# CH32V303VCT6-R1.net
KiCad netlist of a schematic drawn in Altium Designer
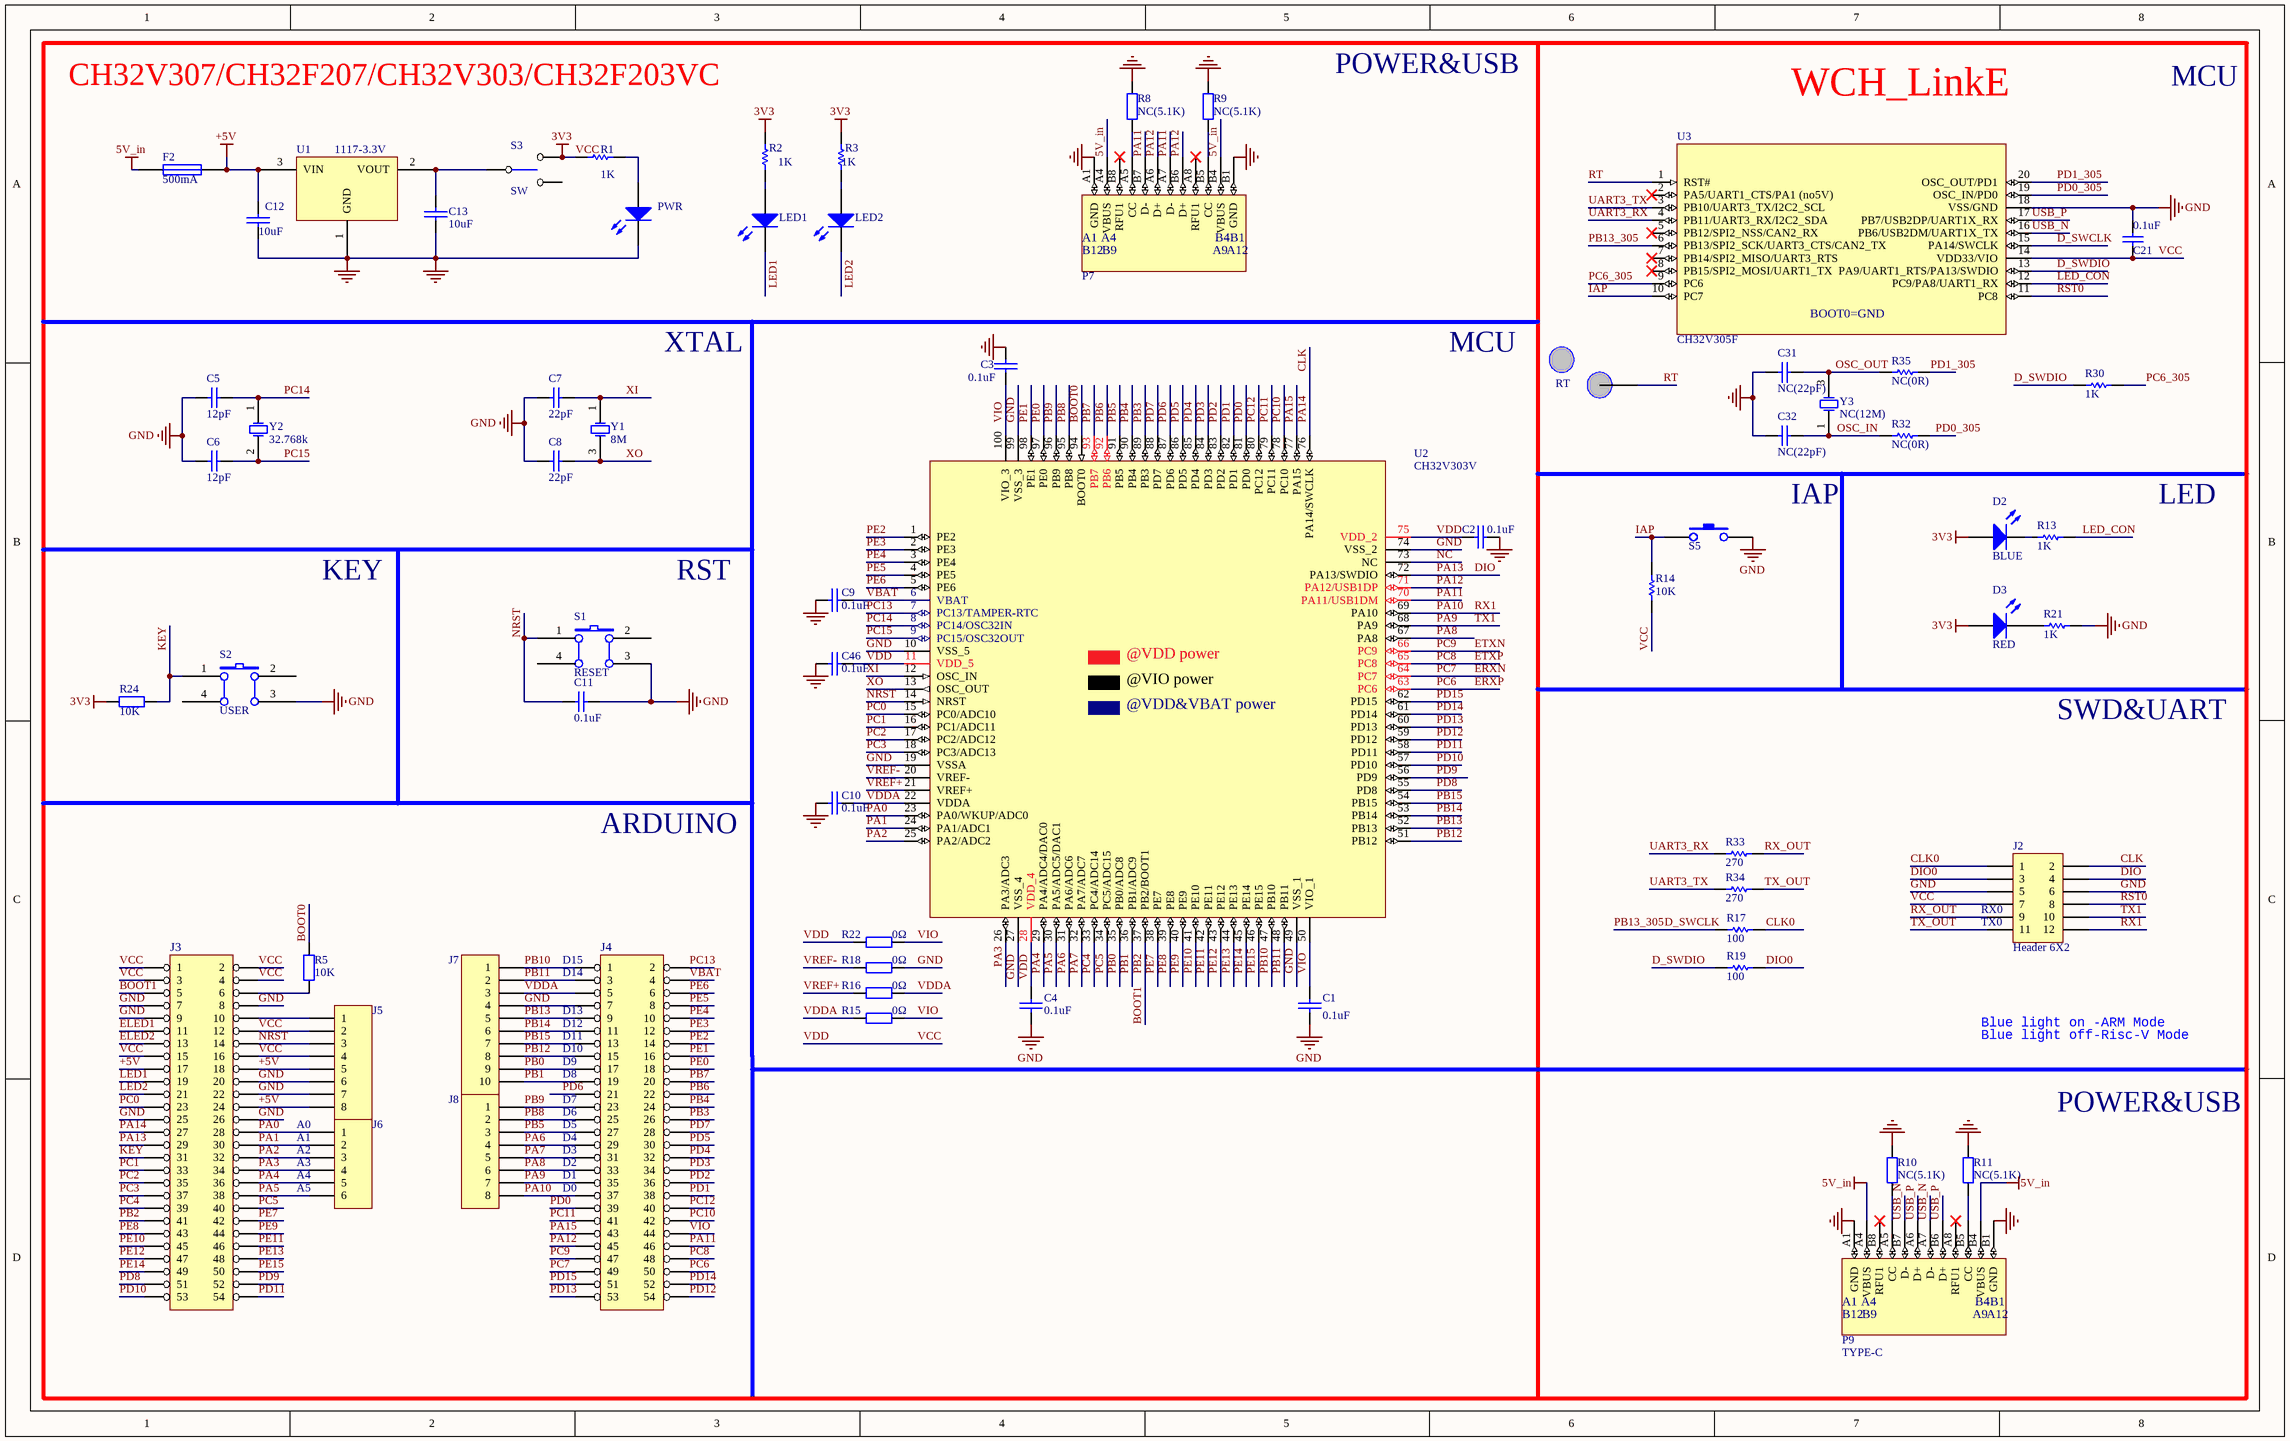
[diagram p0: CH32V303VCT6-R1.SchDoc]

(export (version "E")
  (design (tool "Eeschema 10.0.6"))
  (components
    (comp (ref "C1")
      (value "0.1uF")
      (footprint "0603_C")
      (description "Capacitor")
      (libsource (lib "*") (part "CAP"))
    )
    (comp (ref "C2")
      (value "0.1uF")
      (footprint "0603_C")
      (description "Capacitor")
      (libsource (lib "*") (part "CAP"))
    )
    (comp (ref "C3")
      (value "0.1uF")
      (footprint "0603_C")
      (description "Capacitor")
      (libsource (lib "*") (part "CAP"))
    )
    (comp (ref "C4")
      (value "0.1uF")
      (footprint "0603_C")
      (description "Capacitor")
      (libsource (lib "*") (part "CAP"))
    )
    (comp (ref "C5")
      (value "12pF")
      (footprint "0603_C")
      (description "Capacitor")
      (libsource (lib "Miscellaneous Devices") (part "Cap"))
    )
    (comp (ref "C6")
      (value "12pF")
      (footprint "0603_C")
      (description "Capacitor")
      (libsource (lib "Miscellaneous Devices") (part "Cap"))
    )
    (comp (ref "C7")
      (value "22pF")
      (footprint "0603_C")
      (description "Capacitor")
      (libsource (lib "Miscellaneous Devices") (part "Cap"))
    )
    (comp (ref "C8")
      (value "22pF")
      (footprint "0603_C")
      (description "Capacitor")
      (libsource (lib "Miscellaneous Devices") (part "Cap"))
    )
    (comp (ref "C9")
      (value "0.1uF")
      (footprint "0603_C")
      (description "Capacitor")
      (libsource (lib "*") (part "CAP"))
    )
    (comp (ref "C10")
      (value "0.1uF")
      (footprint "0603_C")
      (description "Capacitor")
      (libsource (lib "*") (part "CAP"))
    )
    (comp (ref "C11")
      (value "0.1uF")
      (footprint "0603_C")
      (description "Capacitor")
      (libsource (lib "Miscellaneous Devices") (part "Cap"))
    )
    (comp (ref "C12")
      (value "10uF")
      (footprint "3216_C")
      (description "Capacitor")
      (libsource (lib "*") (part "CAP"))
    )
    (comp (ref "C13")
      (value "10uF")
      (footprint "3216_C")
      (description "Capacitor")
      (libsource (lib "*") (part "CAP"))
    )
    (comp (ref "C21")
      (value "0.1uF")
      (footprint "0603_C")
      (description "Capacitor")
      (libsource (lib "Miscellaneous Devices") (part "Cap"))
    )
    (comp (ref "C31")
      (value "NC(22pF)")
      (footprint "0603_C")
      (description "Capacitor")
      (fields (field (name "PUBLISHER") "Altium Limited"))
      (libsource (lib "*") (part "Cap"))
    )
    (comp (ref "C32")
      (value "NC(22pF)")
      (footprint "0603_C")
      (description "Capacitor")
      (fields (field (name "PUBLISHER") "Altium Limited"))
      (libsource (lib "*") (part "Cap"))
    )
    (comp (ref "C46")
      (value "0.1uF")
      (footprint "0603_C")
      (description "Capacitor")
      (libsource (lib "*") (part "CAP"))
    )
    (comp (ref "D2")
      (value "BLUE")
      (footprint "0603+")
      (description "Typical RED, GREEN, YELLOW, AMBER GaAs LED")
      (fields (field (name "PUBLISHER") "Altium Limited"))
      (libsource (lib "MYLIB") (part "D0603"))
    )
    (comp (ref "D3")
      (value "RED")
      (footprint "0603+")
      (description "Typical RED, GREEN, YELLOW, AMBER GaAs LED")
      (fields (field (name "PUBLISHER") "Altium Limited"))
      (libsource (lib "MYLIB") (part "D0603"))
    )
    (comp (ref "F2")
      (value "500mA")
      (footprint "0805")
      (description "Fuse")
      (libsource (lib "*") (part "FUSE1"))
    )
    (comp (ref "J2")
      (value "Header 6X2")
      (footprint "IDC12-2.54mm")
      (description "Header, 6-Pin, Dual row")
      (fields (field (name "PUBLISHER") "Altium Limited"))
      (libsource (lib "Miscellaneous Connectors") (part "Header 6X2"))
    )
    (comp (ref "J3")
      (value "HEADER 27x2")
      (footprint "MYPCB:IDC54-2.54MM")
      (description "Header, 27-Pin, Dual row")
      (libsource (lib "wch_sch_others") (part "HEADER 27x2"))
    )
    (comp (ref "J4")
      (value "HEADER 27x2")
      (footprint "MYPCB:IDC54-2.54MM")
      (description "Header, 27-Pin, Dual row")
      (libsource (lib "wch_sch_others") (part "HEADER 27x2"))
    )
    (comp (ref "J5")
      (value "Header 8")
      (footprint "SIP8-2.54mm")
      (description "Header, 8-Pin")
      (fields (field (name "PUBLISHER") "Altium Limited"))
      (libsource (lib "Miscellaneous Connectors") (part "Header 8"))
    )
    (comp (ref "J6")
      (value "Header 6")
      (footprint "SIP6-2.54MM")
      (description "Header, 6-Pin")
      (fields (field (name "PUBLISHER") "Altium Limited"))
      (libsource (lib "Miscellaneous Connectors") (part "Header 6"))
    )
    (comp (ref "J7")
      (value "Header 10")
      (footprint "SIP10-2.54mm")
      (description "Header, 10-Pin")
      (fields (field (name "PUBLISHER") "Altium Limited"))
      (libsource (lib "Miscellaneous Connectors") (part "Header 10"))
    )
    (comp (ref "J8")
      (value "Header 8")
      (footprint "SIP8-2.54mm")
      (description "Header, 8-Pin")
      (fields (field (name "PUBLISHER") "Altium Limited"))
      (libsource (lib "") (part "Header 8_1"))
    )
    (comp (ref "LED1")
      (value "LED1   blue")
      (footprint "0603+")
      (description "Typical INFRARED GaAs LED")
      (fields (field (name "PUBLISHER") "Altium Limited"))
      (libsource (lib "Miscellaneous Devices") (part "LED0"))
    )
    (comp (ref "LED2")
      (value "LED2  blue")
      (footprint "0603+")
      (description "Typical INFRARED GaAs LED")
      (fields (field (name "PUBLISHER") "Altium Limited"))
      (libsource (lib "Miscellaneous Devices") (part "LED0"))
    )
    (comp (ref "P7")
      (value "USBFS")
      (footprint "TYPE-C-Receptacle-2.0")
      (libsource (lib "*") (part "TYPE-C1"))
    )
    (comp (ref "P9")
      (value "TYPE-C")
      (footprint "TYPE-C-Receptacle-2.0")
      (libsource (lib "*") (part "TYPE-C1"))
    )
    (comp (ref "PWR")
      (value "POWER  red")
      (footprint "0603+")
      (description "Typical INFRARED GaAs LED")
      (fields (field (name "PUBLISHER") "Altium Limited"))
      (libsource (lib "Miscellaneous Devices") (part "LED0"))
    )
    (comp (ref "R1")
      (value "1K")
      (footprint "0603")
      (description "Semiconductor Resistor")
      (libsource (lib "Miscellaneous Devices") (part "Res Semi"))
    )
    (comp (ref "R2")
      (value "1K")
      (footprint "0603")
      (description "Semiconductor Resistor")
      (libsource (lib "Miscellaneous Devices") (part "Res Semi"))
    )
    (comp (ref "R3")
      (value "1K")
      (footprint "0603")
      (description "Semiconductor Resistor")
      (libsource (lib "Miscellaneous Devices") (part "Res Semi"))
    )
    (comp (ref "R5")
      (value "10K")
      (footprint "0603")
      (description "Resistor")
      (libsource (lib "") (part "Res2_2"))
    )
    (comp (ref "R8")
      (value "NC(5.1K)")
      (footprint "0603")
      (description "Resistor")
      (libsource (lib "Miscellaneous Devices") (part "Res2"))
    )
    (comp (ref "R9")
      (value "NC(5.1K)")
      (footprint "0603")
      (description "Resistor")
      (libsource (lib "Miscellaneous Devices") (part "Res2"))
    )
    (comp (ref "R10")
      (value "NC(5.1K)")
      (footprint "0603")
      (description "Resistor")
      (libsource (lib "") (part "Res2_2"))
    )
    (comp (ref "R11")
      (value "NC(5.1K)")
      (footprint "0603")
      (description "Resistor")
      (libsource (lib "") (part "Res2_2"))
    )
    (comp (ref "R13")
      (value "1K")
      (footprint "0603")
      (description "Resistor")
      (fields (field (name "PUBLISHER") "Altium Limited"))
      (libsource (lib "MYLIB") (part "0603-1"))
    )
    (comp (ref "R14")
      (value "10K")
      (footprint "0603")
      (description "Resistor")
      (fields (field (name "PUBLISHER") "Altium Limited"))
      (libsource (lib "MYLIB") (part "0603-1"))
    )
    (comp (ref "R15")
      (value "0Ω")
      (footprint "0603")
      (description "Resistor")
      (libsource (lib "") (part "Res2_1"))
    )
    (comp (ref "R16")
      (value "0Ω")
      (footprint "0603")
      (description "Resistor")
      (libsource (lib "") (part "Res2_1"))
    )
    (comp (ref "R17")
      (value "100")
      (footprint "0603")
      (description "Resistor")
      (fields (field (name "PUBLISHER") "Altium Limited"))
      (libsource (lib "MYLIB") (part "0603-1"))
    )
    (comp (ref "R18")
      (value "0Ω")
      (footprint "0603")
      (description "Resistor")
      (libsource (lib "") (part "Res2_1"))
    )
    (comp (ref "R19")
      (value "100")
      (footprint "0603")
      (description "Resistor")
      (fields (field (name "PUBLISHER") "Altium Limited"))
      (libsource (lib "MYLIB") (part "0603-1"))
    )
    (comp (ref "R21")
      (value "1K")
      (footprint "0603")
      (description "Resistor")
      (fields (field (name "PUBLISHER") "Altium Limited"))
      (libsource (lib "MYLIB") (part "0603-1"))
    )
    (comp (ref "R22")
      (value "0Ω")
      (footprint "0603")
      (description "Resistor")
      (libsource (lib "") (part "Res2_1"))
    )
    (comp (ref "R24")
      (value "10K")
      (footprint "0603")
      (description "Resistor")
      (libsource (lib "") (part "Res2_1"))
    )
    (comp (ref "R30")
      (value "1K")
      (footprint "0603")
      (description "Resistor")
      (fields (field (name "PUBLISHER") "Altium Limited"))
      (libsource (lib "MYLIB") (part "0603-1"))
    )
    (comp (ref "R32")
      (value "NC(0R)")
      (footprint "0603")
      (description "Resistor")
      (fields (field (name "PUBLISHER") "Altium Limited"))
      (libsource (lib "MYLIB") (part "0603-1"))
    )
    (comp (ref "R33")
      (value "270")
      (footprint "0603")
      (description "Resistor")
      (fields (field (name "PUBLISHER") "Altium Limited"))
      (libsource (lib "MYLIB") (part "0603-1"))
    )
    (comp (ref "R34")
      (value "270")
      (footprint "0603")
      (description "Resistor")
      (fields (field (name "PUBLISHER") "Altium Limited"))
      (libsource (lib "MYLIB") (part "0603-1"))
    )
    (comp (ref "R35")
      (value "NC(0R)")
      (footprint "0603")
      (description "Resistor")
      (fields (field (name "PUBLISHER") "Altium Limited"))
      (libsource (lib "MYLIB") (part "0603-1"))
    )
    (comp (ref "RT")
      (value "Testpoint")
      (footprint "TESTPOINT1")
      (description "测试点")
      (libsource (lib "wch_sch_others") (part "Testpoint"))
    )
    (comp (ref "S1")
      (value "RESET")
      (footprint "KEYX")
      (description "SE PUSHBUTTON")
      (libsource (lib "Documents") (part "SW PUSHBUTTON"))
    )
    (comp (ref "S2")
      (value "USER")
      (footprint "KEYX")
      (description "SE PUSHBUTTON")
      (libsource (lib "Documents") (part "SW PUSHBUTTON"))
    )
    (comp (ref "S3") (value "SW") (footprint "SW1") (libsource (lib "MYSCH") (part "SW")))
    (comp (ref "S5") (value "KEY") (footprint "贴片按键") (libsource (lib "*") (part "KEY")))
    (comp (ref "U1")
      (value "1117-3.3V")
      (footprint "SOT-223")
      (libsource (lib "wch_sch_others") (part "1117-3.3V"))
    )
    (comp (ref "U2")
      (value "CH32V303V")
      (footprint "LQFP100")
      (description "RISC-V FPU HD-MCU, 144MHz, 8*UART, 10*Timer, 4*OPA")
      (libsource (lib "CHXXX") (part "CH32V303V"))
    )
    (comp (ref "U3")
      (value "CH32V305F")
      (footprint "TSSOP20")
      (description "RISC-V FPU HD-MCU, 144MHz, USB_480M, CAN, UART*2, SPI")
      (libsource (lib "CHXXX") (part "CH32V305F"))
    )
    (comp (ref "Y1")
      (value "8M")
      (footprint "XT3225")
      (description "Crystal Oscillator")
      (fields (field (name "PUBLISHER") "Altium Limited"))
      (libsource (lib "") (part "XTAL_1"))
    )
    (comp (ref "Y2")
      (value "32.768k")
      (footprint "FC-135")
      (description "Crystal Oscillator")
      (fields (field (name "PUBLISHER") "Altium Limited"))
      (libsource (lib "Miscellaneous Devices") (part "XTAL"))
    )
    (comp (ref "Y3")
      (value "NC(12M)")
      (footprint "XT3225")
      (description "Crystal Oscillator")
      (libsource (lib "*") (part "XTAL"))
    )
  )
  (nets
    (net (code "1") (name "+5V") (class "Default")
      (node (ref "C12") (pin "1") (pinfunction "1_1") (pintype "passive"))
      (node (ref "F2") (pin "2") (pinfunction "2_2") (pintype "passive"))
      (node (ref "J3") (pin "17") (pinfunction "17_17") (pintype "passive"))
      (node (ref "J3") (pin "18") (pinfunction "18_18") (pintype "passive"))
      (node (ref "J3") (pin "24") (pinfunction "24_24") (pintype "passive"))
      (node (ref "J5") (pin "5") (pinfunction "5_5") (pintype "passive"))
      (node (ref "J5") (pin "8") (pinfunction "8_8") (pintype "passive"))
      (node (ref "U1") (pin "3") (pinfunction "VIN_3") (pintype "passive"))
    )
    (net (code "2") (name "/BOOT0") (class "Default")
      (node (ref "R5") (pin "2") (pinfunction "2_2") (pintype "passive"))
      (node (ref "U2") (pin "94") (pinfunction "BOOT0_94") (pintype "input"))
    )
    (net (code "3") (name "/BOOT1") (class "Default")
      (node (ref "J3") (pin "41") (pinfunction "41_41") (pintype "passive"))
      (node (ref "J3") (pin "5") (pinfunction "5_5") (pintype "passive"))
      (node (ref "U2") (pin "37") (pinfunction "PB2/BOOT1_37") (pintype "bidirectional"))
    )
    (net (code "4") (name "/CLK") (class "Default")
      (node (ref "J2") (pin "2") (pinfunction "2_2") (pintype "passive"))
      (node (ref "J3") (pin "27") (pinfunction "27_27") (pintype "passive"))
      (node (ref "U2") (pin "76") (pinfunction "PA14/SWCLK_76") (pintype "bidirectional"))
    )
    (net (code "5") (name "/CLK0") (class "Default")
      (node (ref "J2") (pin "1") (pinfunction "1_1") (pintype "passive"))
      (node (ref "R17") (pin "1") (pinfunction "1_1") (pintype "passive"))
    )
    (net (code "6") (name "/DIO") (class "Default")
      (node (ref "J2") (pin "4") (pinfunction "4_4") (pintype "passive"))
      (node (ref "J3") (pin "29") (pinfunction "29_29") (pintype "passive"))
      (node (ref "U2") (pin "72") (pinfunction "PA13/SWDIO_72") (pintype "bidirectional"))
    )
    (net (code "7") (name "/DIO0") (class "Default")
      (node (ref "J2") (pin "3") (pinfunction "3_3") (pintype "passive"))
      (node (ref "R19") (pin "1") (pinfunction "1_1") (pintype "passive"))
    )
    (net (code "8") (name "/D_SWCLK") (class "Default")
      (node (ref "R17") (pin "2") (pinfunction "2_2") (pintype "passive"))
      (node (ref "U3") (pin "15") (pinfunction "PA14/SWCLK_15") (pintype "bidirectional"))
      (node (ref "U3") (pin "6") (pinfunction "PB13/SPI2_SCK/UART3_CTS/CAN2_TX_6") (pintype "bidirectional"))
    )
    (net (code "9") (name "/D_SWDIO") (class "Default")
      (node (ref "R19") (pin "2") (pinfunction "2_2") (pintype "passive"))
      (node (ref "R30") (pin "1") (pinfunction "1_1") (pintype "passive"))
      (node (ref "U3") (pin "13") (pinfunction "PA9/UART1_RTS/PA13/SWDIO_13") (pintype "bidirectional"))
    )
    (net (code "10") (name "/ELED1") (class "Default")
      (node (ref "J3") (pin "11") (pinfunction "11_11") (pintype "passive"))
    )
    (net (code "11") (name "/ELED2") (class "Default")
      (node (ref "J3") (pin "13") (pinfunction "13_13") (pintype "passive"))
    )
    (net (code "12") (name "/ERXN") (class "Default")
      (node (ref "J4") (pin "49") (pinfunction "49_49") (pintype "passive"))
      (node (ref "U2") (pin "64") (pinfunction "PC7_64") (pintype "bidirectional"))
    )
    (net (code "13") (name "/ERXP") (class "Default")
      (node (ref "J4") (pin "50") (pinfunction "50_50") (pintype "passive"))
      (node (ref "U2") (pin "63") (pinfunction "PC6_63") (pintype "bidirectional"))
    )
    (net (code "14") (name "/ETXN") (class "Default")
      (node (ref "J4") (pin "47") (pinfunction "47_47") (pintype "passive"))
      (node (ref "U2") (pin "66") (pinfunction "PC9_66") (pintype "bidirectional"))
    )
    (net (code "15") (name "/ETXP") (class "Default")
      (node (ref "J4") (pin "48") (pinfunction "48_48") (pintype "passive"))
      (node (ref "U2") (pin "65") (pinfunction "PC8_65") (pintype "bidirectional"))
    )
    (net (code "16") (name "/IAP") (class "Default")
      (node (ref "R14") (pin "1") (pinfunction "1_1") (pintype "passive"))
      (node (ref "S5") (pin "1") (pinfunction "1_1") (pintype "passive"))
      (node (ref "U3") (pin "10") (pinfunction "PC7_10") (pintype "bidirectional"))
    )
    (net (code "17") (name "/KEY") (class "Default")
      (node (ref "J3") (pin "31") (pinfunction "31_31") (pintype "passive"))
      (node (ref "R24") (pin "1") (pinfunction "1_1") (pintype "passive"))
      (node (ref "S2") (pin "1") (pinfunction "A0_1") (pintype "passive"))
    )
    (net (code "18") (name "/LED1") (class "Default")
      (node (ref "J3") (pin "19") (pinfunction "19_19") (pintype "passive"))
      (node (ref "LED1") (pin "2") (pinfunction "K_2") (pintype "passive"))
    )
    (net (code "19") (name "/LED2") (class "Default")
      (node (ref "J3") (pin "21") (pinfunction "21_21") (pintype "passive"))
      (node (ref "LED2") (pin "2") (pinfunction "K_2") (pintype "passive"))
    )
    (net (code "20") (name "/LED_CON") (class "Default")
      (node (ref "R13") (pin "1") (pinfunction "1_1") (pintype "passive"))
      (node (ref "U3") (pin "12") (pinfunction "PC9/PA8/UART1_RX_12") (pintype "bidirectional"))
    )
    (net (code "21") (name "/NC") (class "Default")
      (node (ref "U2") (pin "73") (pinfunction "NC_73") (pintype "tri_state"))
    )
    (net (code "22") (name "/NRST") (class "Default")
      (node (ref "C11") (pin "2") (pinfunction "2_2") (pintype "passive"))
      (node (ref "J3") (pin "14") (pinfunction "14_14") (pintype "passive"))
      (node (ref "J5") (pin "3") (pinfunction "3_3") (pintype "passive"))
      (node (ref "S1") (pin "1") (pinfunction "A0_1") (pintype "passive"))
      (node (ref "U2") (pin "14") (pinfunction "NRST_14") (pintype "input"))
    )
    (net (code "23") (name "/OSC_IN") (class "Default")
      (node (ref "C32") (pin "2") (pinfunction "2_2") (pintype "passive"))
      (node (ref "R32") (pin "2") (pinfunction "2_2") (pintype "passive"))
      (node (ref "Y3") (pin "1") (pinfunction "OSC1_1") (pintype "passive"))
    )
    (net (code "24") (name "/OSC_OUT") (class "Default")
      (node (ref "C31") (pin "2") (pinfunction "2_2") (pintype "passive"))
      (node (ref "R35") (pin "2") (pinfunction "2_2") (pintype "passive"))
      (node (ref "Y3") (pin "3") (pinfunction "OSC2_3") (pintype "passive"))
    )
    (net (code "25") (name "/PA0") (class "Default")
      (node (ref "J3") (pin "28") (pinfunction "28_28") (pintype "passive"))
      (node (ref "J6") (pin "1") (pinfunction "1_1") (pintype "passive"))
      (node (ref "U2") (pin "23") (pinfunction "PA0/WKUP/ADC0_23") (pintype "bidirectional"))
    )
    (net (code "26") (name "/PA1") (class "Default")
      (node (ref "J3") (pin "30") (pinfunction "30_30") (pintype "passive"))
      (node (ref "J6") (pin "2") (pinfunction "2_2") (pintype "passive"))
      (node (ref "U2") (pin "24") (pinfunction "PA1/ADC1_24") (pintype "bidirectional"))
    )
    (net (code "27") (name "/PA2") (class "Default")
      (node (ref "J3") (pin "32") (pinfunction "32_32") (pintype "passive"))
      (node (ref "J6") (pin "3") (pinfunction "3_3") (pintype "passive"))
      (node (ref "U2") (pin "25") (pinfunction "PA2/ADC2_25") (pintype "bidirectional"))
    )
    (net (code "28") (name "/PA3") (class "Default")
      (node (ref "J3") (pin "34") (pinfunction "34_34") (pintype "passive"))
      (node (ref "J6") (pin "4") (pinfunction "4_4") (pintype "passive"))
      (node (ref "U2") (pin "26") (pinfunction "PA3/ADC3_26") (pintype "bidirectional"))
    )
    (net (code "29") (name "/PA4") (class "Default")
      (node (ref "J3") (pin "36") (pinfunction "36_36") (pintype "passive"))
      (node (ref "J6") (pin "5") (pinfunction "5_5") (pintype "passive"))
      (node (ref "U2") (pin "29") (pinfunction "PA4/ADC4/DAC0_29") (pintype "bidirectional"))
    )
    (net (code "30") (name "/PA5") (class "Default")
      (node (ref "J3") (pin "38") (pinfunction "38_38") (pintype "passive"))
      (node (ref "J6") (pin "6") (pinfunction "6_6") (pintype "passive"))
      (node (ref "U2") (pin "30") (pinfunction "PA5/ADC5/DAC1_30") (pintype "bidirectional"))
    )
    (net (code "31") (name "/PA6") (class "Default")
      (node (ref "J4") (pin "29") (pinfunction "29_29") (pintype "passive"))
      (node (ref "J8") (pin "4") (pinfunction "4_4") (pintype "passive"))
      (node (ref "U2") (pin "31") (pinfunction "PA6/ADC6_31") (pintype "bidirectional"))
    )
    (net (code "32") (name "/PA7") (class "Default")
      (node (ref "J4") (pin "31") (pinfunction "31_31") (pintype "passive"))
      (node (ref "J8") (pin "5") (pinfunction "5_5") (pintype "passive"))
      (node (ref "U2") (pin "32") (pinfunction "PA7/ADC7_32") (pintype "bidirectional"))
    )
    (net (code "33") (name "/PA8") (class "Default")
      (node (ref "J4") (pin "33") (pinfunction "33_33") (pintype "passive"))
      (node (ref "J8") (pin "6") (pinfunction "6_6") (pintype "passive"))
      (node (ref "U2") (pin "67") (pinfunction "PA8_67") (pintype "bidirectional"))
    )
    (net (code "34") (name "/PA9") (class "Default")
      (node (ref "J2") (pin "10") (pinfunction "10_10") (pintype "passive"))
      (node (ref "J4") (pin "35") (pinfunction "35_35") (pintype "passive"))
      (node (ref "J8") (pin "7") (pinfunction "7_7") (pintype "passive"))
      (node (ref "U2") (pin "68") (pinfunction "PA9_68") (pintype "bidirectional"))
    )
    (net (code "35") (name "/PA10") (class "Default")
      (node (ref "J2") (pin "12") (pinfunction "12_12") (pintype "passive"))
      (node (ref "J4") (pin "37") (pinfunction "37_37") (pintype "passive"))
      (node (ref "J8") (pin "8") (pinfunction "8_8") (pintype "passive"))
      (node (ref "U2") (pin "69") (pinfunction "PA10_69") (pintype "bidirectional"))
    )
    (net (code "36") (name "/PA11") (class "Default")
      (node (ref "J4") (pin "46") (pinfunction "46_46") (pintype "passive"))
      (node (ref "P7") (pin "A7") (pinfunction "D-_A7") (pintype "bidirectional"))
      (node (ref "P7") (pin "B7") (pinfunction "D-_B7") (pintype "bidirectional"))
      (node (ref "U2") (pin "70") (pinfunction "PA11/USB1DM_70") (pintype "bidirectional"))
    )
    (net (code "37") (name "/PA12") (class "Default")
      (node (ref "J4") (pin "45") (pinfunction "45_45") (pintype "passive"))
      (node (ref "P7") (pin "A6") (pinfunction "D+_A6") (pintype "bidirectional"))
      (node (ref "P7") (pin "B6") (pinfunction "D+_B6") (pintype "bidirectional"))
      (node (ref "U2") (pin "71") (pinfunction "PA12/USB1DP_71") (pintype "bidirectional"))
    )
    (net (code "38") (name "/PA15") (class "Default")
      (node (ref "J4") (pin "43") (pinfunction "43_43") (pintype "passive"))
      (node (ref "U2") (pin "77") (pinfunction "PA15_77") (pintype "bidirectional"))
    )
    (net (code "39") (name "/PB0") (class "Default")
      (node (ref "J4") (pin "17") (pinfunction "17_17") (pintype "passive"))
      (node (ref "J7") (pin "9") (pinfunction "9_9") (pintype "passive"))
      (node (ref "U2") (pin "35") (pinfunction "PB0/ADC8_35") (pintype "bidirectional"))
    )
    (net (code "40") (name "/PB1") (class "Default")
      (node (ref "J4") (pin "19") (pinfunction "19_19") (pintype "passive"))
      (node (ref "J7") (pin "10") (pinfunction "10_10") (pintype "passive"))
      (node (ref "U2") (pin "36") (pinfunction "PB1/ADC9_36") (pintype "bidirectional"))
    )
    (net (code "41") (name "/PB3") (class "Default")
      (node (ref "J4") (pin "26") (pinfunction "26_26") (pintype "passive"))
      (node (ref "U2") (pin "89") (pinfunction "PB3_89") (pintype "bidirectional"))
    )
    (net (code "42") (name "/PB4") (class "Default")
      (node (ref "J4") (pin "24") (pinfunction "24_24") (pintype "passive"))
      (node (ref "U2") (pin "90") (pinfunction "PB4_90") (pintype "bidirectional"))
    )
    (net (code "43") (name "/PB5") (class "Default")
      (node (ref "J4") (pin "27") (pinfunction "27_27") (pintype "passive"))
      (node (ref "J8") (pin "3") (pinfunction "3_3") (pintype "passive"))
      (node (ref "U2") (pin "91") (pinfunction "PB5_91") (pintype "bidirectional"))
    )
    (net (code "44") (name "/PB6") (class "Default")
      (node (ref "J4") (pin "22") (pinfunction "22_22") (pintype "passive"))
      (node (ref "U2") (pin "92") (pinfunction "PB6_92") (pintype "bidirectional"))
    )
    (net (code "45") (name "/PB7") (class "Default")
      (node (ref "J4") (pin "20") (pinfunction "20_20") (pintype "passive"))
      (node (ref "U2") (pin "93") (pinfunction "PB7_93") (pintype "bidirectional"))
    )
    (net (code "46") (name "/PB8") (class "Default")
      (node (ref "J4") (pin "25") (pinfunction "25_25") (pintype "passive"))
      (node (ref "J8") (pin "2") (pinfunction "2_2") (pintype "passive"))
      (node (ref "U2") (pin "95") (pinfunction "PB8_95") (pintype "bidirectional"))
    )
    (net (code "47") (name "/PB9") (class "Default")
      (node (ref "J4") (pin "23") (pinfunction "23_23") (pintype "passive"))
      (node (ref "J8") (pin "1") (pinfunction "1_1") (pintype "passive"))
      (node (ref "U2") (pin "96") (pinfunction "PB9_96") (pintype "bidirectional"))
    )
    (net (code "48") (name "/PB10") (class "Default")
      (node (ref "J4") (pin "1") (pinfunction "1_1") (pintype "passive"))
      (node (ref "J7") (pin "1") (pinfunction "1_1") (pintype "passive"))
      (node (ref "U2") (pin "47") (pinfunction "PB10_47") (pintype "bidirectional"))
    )
    (net (code "49") (name "/PB11") (class "Default")
      (node (ref "J4") (pin "3") (pinfunction "3_3") (pintype "passive"))
      (node (ref "J7") (pin "2") (pinfunction "2_2") (pintype "passive"))
      (node (ref "U2") (pin "48") (pinfunction "PB11_48") (pintype "bidirectional"))
    )
    (net (code "50") (name "/PB12") (class "Default")
      (node (ref "J4") (pin "15") (pinfunction "15_15") (pintype "passive"))
      (node (ref "J7") (pin "8") (pinfunction "8_8") (pintype "passive"))
      (node (ref "U2") (pin "51") (pinfunction "PB12_51") (pintype "bidirectional"))
    )
    (net (code "51") (name "/PB13") (class "Default")
      (node (ref "J4") (pin "9") (pinfunction "9_9") (pintype "passive"))
      (node (ref "J7") (pin "5") (pinfunction "5_5") (pintype "passive"))
      (node (ref "U2") (pin "52") (pinfunction "PB13_52") (pintype "bidirectional"))
    )
    (net (code "52") (name "/PB14") (class "Default")
      (node (ref "J4") (pin "11") (pinfunction "11_11") (pintype "passive"))
      (node (ref "J7") (pin "6") (pinfunction "6_6") (pintype "passive"))
      (node (ref "U2") (pin "53") (pinfunction "PB14_53") (pintype "bidirectional"))
    )
    (net (code "53") (name "/PB15") (class "Default")
      (node (ref "J4") (pin "13") (pinfunction "13_13") (pintype "passive"))
      (node (ref "J7") (pin "7") (pinfunction "7_7") (pintype "passive"))
      (node (ref "U2") (pin "54") (pinfunction "PB15_54") (pintype "bidirectional"))
    )
    (net (code "54") (name "/PC0") (class "Default")
      (node (ref "J3") (pin "23") (pinfunction "23_23") (pintype "passive"))
      (node (ref "U2") (pin "15") (pinfunction "PC0/ADC10_15") (pintype "bidirectional"))
    )
    (net (code "55") (name "/PC1") (class "Default")
      (node (ref "J3") (pin "33") (pinfunction "33_33") (pintype "passive"))
      (node (ref "U2") (pin "16") (pinfunction "PC1/ADC11_16") (pintype "bidirectional"))
    )
    (net (code "56") (name "/PC2") (class "Default")
      (node (ref "J3") (pin "35") (pinfunction "35_35") (pintype "passive"))
      (node (ref "U2") (pin "17") (pinfunction "PC2/ADC12_17") (pintype "bidirectional"))
    )
    (net (code "57") (name "/PC3") (class "Default")
      (node (ref "J3") (pin "37") (pinfunction "37_37") (pintype "passive"))
      (node (ref "U2") (pin "18") (pinfunction "PC3/ADC13_18") (pintype "bidirectional"))
    )
    (net (code "58") (name "/PC4") (class "Default")
      (node (ref "J3") (pin "39") (pinfunction "39_39") (pintype "passive"))
      (node (ref "U2") (pin "33") (pinfunction "PC4/ADC14_33") (pintype "bidirectional"))
    )
    (net (code "59") (name "/PC5") (class "Default")
      (node (ref "J3") (pin "40") (pinfunction "40_40") (pintype "passive"))
      (node (ref "U2") (pin "34") (pinfunction "PC5/ADC15_34") (pintype "bidirectional"))
    )
    (net (code "60") (name "/PC6_305") (class "Default")
      (node (ref "R30") (pin "2") (pinfunction "2_2") (pintype "passive"))
      (node (ref "U3") (pin "9") (pinfunction "PC6_9") (pintype "bidirectional"))
    )
    (net (code "61") (name "/PC10") (class "Default")
      (node (ref "J4") (pin "42") (pinfunction "42_42") (pintype "passive"))
      (node (ref "U2") (pin "78") (pinfunction "PC10_78") (pintype "bidirectional"))
    )
    (net (code "62") (name "/PC11") (class "Default")
      (node (ref "J4") (pin "41") (pinfunction "41_41") (pintype "passive"))
      (node (ref "U2") (pin "79") (pinfunction "PC11_79") (pintype "bidirectional"))
    )
    (net (code "63") (name "/PC12") (class "Default")
      (node (ref "J4") (pin "40") (pinfunction "40_40") (pintype "passive"))
      (node (ref "U2") (pin "80") (pinfunction "PC12_80") (pintype "bidirectional"))
    )
    (net (code "64") (name "/PC13") (class "Default")
      (node (ref "J4") (pin "2") (pinfunction "2_2") (pintype "passive"))
      (node (ref "U2") (pin "7") (pinfunction "PC13/TAMPER-RTC_7") (pintype "bidirectional"))
    )
    (net (code "65") (name "/PC14") (class "Default")
      (node (ref "C5") (pin "1") (pinfunction "1_1") (pintype "passive"))
      (node (ref "U2") (pin "8") (pinfunction "PC14/OSC32IN_8") (pintype "bidirectional"))
      (node (ref "Y2") (pin "1") (pinfunction "OSC1_1") (pintype "passive"))
    )
    (net (code "66") (name "/PC15") (class "Default")
      (node (ref "C6") (pin "1") (pinfunction "1_1") (pintype "passive"))
      (node (ref "U2") (pin "9") (pinfunction "PC15/OSC32OUT_9") (pintype "bidirectional"))
      (node (ref "Y2") (pin "2") (pinfunction "OSC2_2") (pintype "passive"))
    )
    (net (code "67") (name "/PD0") (class "Default")
      (node (ref "J4") (pin "39") (pinfunction "39_39") (pintype "passive"))
      (node (ref "U2") (pin "81") (pinfunction "PD0_81") (pintype "bidirectional"))
    )
    (net (code "68") (name "/PD0_305") (class "Default")
      (node (ref "R32") (pin "1") (pinfunction "1_1") (pintype "passive"))
      (node (ref "U3") (pin "19") (pinfunction "OSC_IN/PD0_19") (pintype "bidirectional"))
    )
    (net (code "69") (name "/PD1") (class "Default")
      (node (ref "J4") (pin "38") (pinfunction "38_38") (pintype "passive"))
      (node (ref "U2") (pin "82") (pinfunction "PD1_82") (pintype "bidirectional"))
    )
    (net (code "70") (name "/PD1_305") (class "Default")
      (node (ref "R35") (pin "1") (pinfunction "1_1") (pintype "passive"))
      (node (ref "U3") (pin "20") (pinfunction "OSC_OUT/PD1_20") (pintype "bidirectional"))
    )
    (net (code "71") (name "/PD2") (class "Default")
      (node (ref "J4") (pin "36") (pinfunction "36_36") (pintype "passive"))
      (node (ref "U2") (pin "83") (pinfunction "PD2_83") (pintype "bidirectional"))
    )
    (net (code "72") (name "/PD3") (class "Default")
      (node (ref "J4") (pin "34") (pinfunction "34_34") (pintype "passive"))
      (node (ref "U2") (pin "84") (pinfunction "PD3_84") (pintype "bidirectional"))
    )
    (net (code "73") (name "/PD4") (class "Default")
      (node (ref "J4") (pin "32") (pinfunction "32_32") (pintype "passive"))
      (node (ref "U2") (pin "85") (pinfunction "PD4_85") (pintype "bidirectional"))
    )
    (net (code "74") (name "/PD5") (class "Default")
      (node (ref "J4") (pin "30") (pinfunction "30_30") (pintype "passive"))
      (node (ref "U2") (pin "86") (pinfunction "PD5_86") (pintype "bidirectional"))
    )
    (net (code "75") (name "/PD6") (class "Default")
      (node (ref "J4") (pin "21") (pinfunction "21_21") (pintype "passive"))
      (node (ref "U2") (pin "87") (pinfunction "PD6_87") (pintype "bidirectional"))
    )
    (net (code "76") (name "/PD7") (class "Default")
      (node (ref "J4") (pin "28") (pinfunction "28_28") (pintype "passive"))
      (node (ref "U2") (pin "88") (pinfunction "PD7_88") (pintype "bidirectional"))
    )
    (net (code "77") (name "/PD8") (class "Default")
      (node (ref "J3") (pin "51") (pinfunction "51_51") (pintype "passive"))
      (node (ref "U2") (pin "55") (pinfunction "PD8_55") (pintype "bidirectional"))
    )
    (net (code "78") (name "/PD9") (class "Default")
      (node (ref "J3") (pin "52") (pinfunction "52_52") (pintype "passive"))
      (node (ref "U2") (pin "56") (pinfunction "PD9_56") (pintype "bidirectional"))
    )
    (net (code "79") (name "/PD10") (class "Default")
      (node (ref "J3") (pin "53") (pinfunction "53_53") (pintype "passive"))
      (node (ref "U2") (pin "57") (pinfunction "PD10_57") (pintype "bidirectional"))
    )
    (net (code "80") (name "/PD11") (class "Default")
      (node (ref "J3") (pin "54") (pinfunction "54_54") (pintype "passive"))
      (node (ref "U2") (pin "58") (pinfunction "PD11_58") (pintype "bidirectional"))
    )
    (net (code "81") (name "/PD12") (class "Default")
      (node (ref "J4") (pin "54") (pinfunction "54_54") (pintype "passive"))
      (node (ref "U2") (pin "59") (pinfunction "PD12_59") (pintype "bidirectional"))
    )
    (net (code "82") (name "/PD13") (class "Default")
      (node (ref "J4") (pin "53") (pinfunction "53_53") (pintype "passive"))
      (node (ref "U2") (pin "60") (pinfunction "PD13_60") (pintype "bidirectional"))
    )
    (net (code "83") (name "/PD14") (class "Default")
      (node (ref "J4") (pin "52") (pinfunction "52_52") (pintype "passive"))
      (node (ref "U2") (pin "61") (pinfunction "PD14_61") (pintype "bidirectional"))
    )
    (net (code "84") (name "/PD15") (class "Default")
      (node (ref "J4") (pin "51") (pinfunction "51_51") (pintype "passive"))
      (node (ref "U2") (pin "62") (pinfunction "PD15_62") (pintype "bidirectional"))
    )
    (net (code "85") (name "/PE0") (class "Default")
      (node (ref "J4") (pin "18") (pinfunction "18_18") (pintype "passive"))
      (node (ref "U2") (pin "97") (pinfunction "PE0_97") (pintype "bidirectional"))
    )
    (net (code "86") (name "/PE1") (class "Default")
      (node (ref "J4") (pin "16") (pinfunction "16_16") (pintype "passive"))
      (node (ref "U2") (pin "98") (pinfunction "PE1_98") (pintype "bidirectional"))
    )
    (net (code "87") (name "/PE2") (class "Default")
      (node (ref "J4") (pin "14") (pinfunction "14_14") (pintype "passive"))
      (node (ref "U2") (pin "1") (pinfunction "PE2_1") (pintype "bidirectional"))
    )
    (net (code "88") (name "/PE3") (class "Default")
      (node (ref "J4") (pin "12") (pinfunction "12_12") (pintype "passive"))
      (node (ref "U2") (pin "2") (pinfunction "PE3_2") (pintype "bidirectional"))
    )
    (net (code "89") (name "/PE4") (class "Default")
      (node (ref "J4") (pin "10") (pinfunction "10_10") (pintype "passive"))
      (node (ref "U2") (pin "3") (pinfunction "PE4_3") (pintype "bidirectional"))
    )
    (net (code "90") (name "/PE5") (class "Default")
      (node (ref "J4") (pin "8") (pinfunction "8_8") (pintype "passive"))
      (node (ref "U2") (pin "4") (pinfunction "PE5_4") (pintype "bidirectional"))
    )
    (net (code "91") (name "/PE6") (class "Default")
      (node (ref "J4") (pin "6") (pinfunction "6_6") (pintype "passive"))
      (node (ref "U2") (pin "5") (pinfunction "PE6_5") (pintype "bidirectional"))
    )
    (net (code "92") (name "/PE7") (class "Default")
      (node (ref "J3") (pin "42") (pinfunction "42_42") (pintype "passive"))
      (node (ref "U2") (pin "38") (pinfunction "PE7_38") (pintype "bidirectional"))
    )
    (net (code "93") (name "/PE8") (class "Default")
      (node (ref "J3") (pin "43") (pinfunction "43_43") (pintype "passive"))
      (node (ref "U2") (pin "39") (pinfunction "PE8_39") (pintype "bidirectional"))
    )
    (net (code "94") (name "/PE9") (class "Default")
      (node (ref "J3") (pin "44") (pinfunction "44_44") (pintype "passive"))
      (node (ref "U2") (pin "40") (pinfunction "PE9_40") (pintype "bidirectional"))
    )
    (net (code "95") (name "/PE10") (class "Default")
      (node (ref "J3") (pin "45") (pinfunction "45_45") (pintype "passive"))
      (node (ref "U2") (pin "41") (pinfunction "PE10_41") (pintype "bidirectional"))
    )
    (net (code "96") (name "/PE11") (class "Default")
      (node (ref "J3") (pin "46") (pinfunction "46_46") (pintype "passive"))
      (node (ref "U2") (pin "42") (pinfunction "PE11_42") (pintype "bidirectional"))
    )
    (net (code "97") (name "/PE12") (class "Default")
      (node (ref "J3") (pin "47") (pinfunction "47_47") (pintype "passive"))
      (node (ref "U2") (pin "43") (pinfunction "PE12_43") (pintype "bidirectional"))
    )
    (net (code "98") (name "/PE13") (class "Default")
      (node (ref "J3") (pin "48") (pinfunction "48_48") (pintype "passive"))
      (node (ref "U2") (pin "44") (pinfunction "PE13_44") (pintype "bidirectional"))
    )
    (net (code "99") (name "/PE14") (class "Default")
      (node (ref "J3") (pin "49") (pinfunction "49_49") (pintype "passive"))
      (node (ref "U2") (pin "45") (pinfunction "PE14_45") (pintype "bidirectional"))
    )
    (net (code "100") (name "/PE15") (class "Default")
      (node (ref "J3") (pin "50") (pinfunction "50_50") (pintype "passive"))
      (node (ref "U2") (pin "46") (pinfunction "PE15_46") (pintype "bidirectional"))
    )
    (net (code "101") (name "/RST0") (class "Default")
      (node (ref "J2") (pin "8") (pinfunction "8_8") (pintype "passive"))
      (node (ref "U3") (pin "11") (pinfunction "PC8_11") (pintype "bidirectional"))
    )
    (net (code "102") (name "/RT") (class "Default")
      (node (ref "RT") (pin "1") (pinfunction "point_1") (pintype "passive"))
      (node (ref "U3") (pin "1") (pinfunction "RST#_1") (pintype "input"))
    )
    (net (code "103") (name "/RX_OUT") (class "Default")
      (node (ref "J2") (pin "9") (pinfunction "9_9") (pintype "passive"))
      (node (ref "R33") (pin "1") (pinfunction "1_1") (pintype "passive"))
    )
    (net (code "104") (name "/TX_OUT") (class "Default")
      (node (ref "J2") (pin "11") (pinfunction "11_11") (pintype "passive"))
      (node (ref "R34") (pin "1") (pinfunction "1_1") (pintype "passive"))
    )
    (net (code "105") (name "/UART3_RX") (class "Default")
      (node (ref "R33") (pin "2") (pinfunction "2_2") (pintype "passive"))
      (node (ref "U3") (pin "4") (pinfunction "PB11/UART3_RX/I2C2_SDA_4") (pintype "bidirectional"))
    )
    (net (code "106") (name "/UART3_TX") (class "Default")
      (node (ref "R34") (pin "2") (pinfunction "2_2") (pintype "passive"))
      (node (ref "U3") (pin "3") (pinfunction "PB10/UART3_TX/I2C2_SCL_3") (pintype "bidirectional"))
    )
    (net (code "107") (name "/USB_N") (class "Default")
      (node (ref "P9") (pin "A7") (pinfunction "D-_A7") (pintype "bidirectional"))
      (node (ref "P9") (pin "B7") (pinfunction "D-_B7") (pintype "bidirectional"))
      (node (ref "U3") (pin "16") (pinfunction "PB6/USB2DM/UART1X_TX_16") (pintype "bidirectional"))
    )
    (net (code "108") (name "/USB_P") (class "Default")
      (node (ref "P9") (pin "A6") (pinfunction "D+_A6") (pintype "bidirectional"))
      (node (ref "P9") (pin "B6") (pinfunction "D+_B6") (pintype "bidirectional"))
      (node (ref "U3") (pin "17") (pinfunction "PB7/USB2DP/UART1X_RX_17") (pintype "bidirectional"))
    )
    (net (code "109") (name "/VBAT") (class "Default")
      (node (ref "C9") (pin "2") (pinfunction "2_2") (pintype "passive"))
      (node (ref "J4") (pin "4") (pinfunction "4_4") (pintype "passive"))
      (node (ref "U2") (pin "6") (pinfunction "VBAT_6") (pintype "power_in"))
    )
    (net (code "110") (name "/VDDA") (class "Default")
      (node (ref "C10") (pin "2") (pinfunction "2_2") (pintype "passive"))
      (node (ref "J4") (pin "5") (pinfunction "5_5") (pintype "passive"))
      (node (ref "J7") (pin "3") (pinfunction "3_3") (pintype "passive"))
      (node (ref "R15") (pin "2") (pinfunction "2_2") (pintype "passive"))
      (node (ref "R16") (pin "1") (pinfunction "1_1") (pintype "passive"))
      (node (ref "U2") (pin "22") (pinfunction "VDDA_22") (pintype "power_in"))
    )
    (net (code "111") (name "/VIO") (class "Default")
      (node (ref "C1") (pin "2") (pinfunction "2_2") (pintype "passive"))
      (node (ref "C3") (pin "1") (pinfunction "1_1") (pintype "passive"))
      (node (ref "J4") (pin "44") (pinfunction "44_44") (pintype "passive"))
      (node (ref "R15") (pin "1") (pinfunction "1_1") (pintype "passive"))
      (node (ref "R22") (pin "1") (pinfunction "1_1") (pintype "passive"))
      (node (ref "U2") (pin "100") (pinfunction "VIO_3_100") (pintype "power_in"))
      (node (ref "U2") (pin "50") (pinfunction "VIO_1_50") (pintype "power_in"))
    )
    (net (code "112") (name "/VREF+") (class "Default")
      (node (ref "R16") (pin "2") (pinfunction "2_2") (pintype "passive"))
      (node (ref "U2") (pin "21") (pinfunction "VREF+_21") (pintype "power_in"))
    )
    (net (code "113") (name "/VREF-") (class "Default")
      (node (ref "R18") (pin "2") (pinfunction "2_2") (pintype "passive"))
      (node (ref "U2") (pin "20") (pinfunction "VREF-_20") (pintype "power_in"))
    )
    (net (code "114") (name "/XI") (class "Default")
      (node (ref "C7") (pin "2") (pinfunction "2_2") (pintype "passive"))
      (node (ref "U2") (pin "12") (pinfunction "OSC_IN_12") (pintype "input"))
      (node (ref "Y1") (pin "1") (pinfunction "OSC1_1") (pintype "passive"))
    )
    (net (code "115") (name "/XO") (class "Default")
      (node (ref "C8") (pin "2") (pinfunction "2_2") (pintype "passive"))
      (node (ref "U2") (pin "13") (pinfunction "OSC_OUT_13") (pintype "output"))
      (node (ref "Y1") (pin "3") (pinfunction "OSC2_3") (pintype "passive"))
    )
    (net (code "116") (name "3V3") (class "Default")
      (node (ref "C2") (pin "2") (pinfunction "2_2") (pintype "passive"))
      (node (ref "C21") (pin "1") (pinfunction "1_1") (pintype "passive"))
      (node (ref "C4") (pin "2") (pinfunction "2_2") (pintype "passive"))
      (node (ref "C46") (pin "1") (pinfunction "1_1") (pintype "passive"))
      (node (ref "D2") (pin "1") (pinfunction "A_1") (pintype "passive"))
      (node (ref "D3") (pin "1") (pinfunction "A_1") (pintype "passive"))
      (node (ref "J2") (pin "7") (pinfunction "7_7") (pintype "passive"))
      (node (ref "J3") (pin "1") (pinfunction "1_1") (pintype "passive"))
      (node (ref "J3") (pin "12") (pinfunction "12_12") (pintype "passive"))
      (node (ref "J3") (pin "15") (pinfunction "15_15") (pintype "passive"))
      (node (ref "J3") (pin "16") (pinfunction "16_16") (pintype "passive"))
      (node (ref "J3") (pin "2") (pinfunction "2_2") (pintype "passive"))
      (node (ref "J3") (pin "3") (pinfunction "3_3") (pintype "passive"))
      (node (ref "J3") (pin "4") (pinfunction "4_4") (pintype "passive"))
      (node (ref "J5") (pin "2") (pinfunction "2_2") (pintype "passive"))
      (node (ref "J5") (pin "4") (pinfunction "4_4") (pintype "passive"))
      (node (ref "R1") (pin "2") (pinfunction "2_2") (pintype "passive"))
      (node (ref "R14") (pin "2") (pinfunction "2_2") (pintype "passive"))
      (node (ref "R2") (pin "1") (pinfunction "1_1") (pintype "passive"))
      (node (ref "R22") (pin "2") (pinfunction "2_2") (pintype "passive"))
      (node (ref "R24") (pin "2") (pinfunction "2_2") (pintype "passive"))
      (node (ref "R3") (pin "1") (pinfunction "1_1") (pintype "passive"))
      (node (ref "S3") (pin "3") (pinfunction "3_3") (pintype "passive"))
      (node (ref "U2") (pin "11") (pinfunction "VDD_5_11") (pintype "power_in"))
      (node (ref "U2") (pin "28") (pinfunction "VDD_4_28") (pintype "power_in"))
      (node (ref "U2") (pin "75") (pinfunction "VDD_2_75") (pintype "power_in"))
      (node (ref "U3") (pin "14") (pinfunction "VDD33/VIO_14") (pintype "power_in"))
    )
    (net (code "117") (name "5V_in") (class "Default")
      (node (ref "F2") (pin "1") (pinfunction "1_1") (pintype "passive"))
      (node (ref "P7") (pin "A4") (pinfunction "VBUS_A4") (pintype "bidirectional"))
      (node (ref "P7") (pin "B4") (pinfunction "VBUS_B4") (pintype "bidirectional"))
      (node (ref "P9") (pin "A4") (pinfunction "VBUS_A4") (pintype "bidirectional"))
      (node (ref "P9") (pin "B4") (pinfunction "VBUS_B4") (pintype "bidirectional"))
    )
    (net (code "118") (name "GND") (class "Default")
      (node (ref "C1") (pin "1") (pinfunction "1_1") (pintype "passive"))
      (node (ref "C10") (pin "1") (pinfunction "1_1") (pintype "passive"))
      (node (ref "C11") (pin "1") (pinfunction "1_1") (pintype "passive"))
      (node (ref "C12") (pin "2") (pinfunction "2_2") (pintype "passive"))
      (node (ref "C13") (pin "2") (pinfunction "2_2") (pintype "passive"))
      (node (ref "C2") (pin "1") (pinfunction "1_1") (pintype "passive"))
      (node (ref "C21") (pin "2") (pinfunction "2_2") (pintype "passive"))
      (node (ref "C3") (pin "2") (pinfunction "2_2") (pintype "passive"))
      (node (ref "C31") (pin "1") (pinfunction "1_1") (pintype "passive"))
      (node (ref "C32") (pin "1") (pinfunction "1_1") (pintype "passive"))
      (node (ref "C4") (pin "1") (pinfunction "1_1") (pintype "passive"))
      (node (ref "C46") (pin "2") (pinfunction "2_2") (pintype "passive"))
      (node (ref "C5") (pin "2") (pinfunction "2_2") (pintype "passive"))
      (node (ref "C6") (pin "2") (pinfunction "2_2") (pintype "passive"))
      (node (ref "C7") (pin "1") (pinfunction "1_1") (pintype "passive"))
      (node (ref "C8") (pin "1") (pinfunction "1_1") (pintype "passive"))
      (node (ref "C9") (pin "1") (pinfunction "1_1") (pintype "passive"))
      (node (ref "J2") (pin "5") (pinfunction "5_5") (pintype "passive"))
      (node (ref "J2") (pin "6") (pinfunction "6_6") (pintype "passive"))
      (node (ref "J3") (pin "20") (pinfunction "20_20") (pintype "passive"))
      (node (ref "J3") (pin "22") (pinfunction "22_22") (pintype "passive"))
      (node (ref "J3") (pin "25") (pinfunction "25_25") (pintype "passive"))
      (node (ref "J3") (pin "26") (pinfunction "26_26") (pintype "passive"))
      (node (ref "J3") (pin "7") (pinfunction "7_7") (pintype "passive"))
      (node (ref "J3") (pin "8") (pinfunction "8_8") (pintype "passive"))
      (node (ref "J3") (pin "9") (pinfunction "9_9") (pintype "passive"))
      (node (ref "J4") (pin "7") (pinfunction "7_7") (pintype "passive"))
      (node (ref "J5") (pin "6") (pinfunction "6_6") (pintype "passive"))
      (node (ref "J5") (pin "7") (pinfunction "7_7") (pintype "passive"))
      (node (ref "J7") (pin "4") (pinfunction "4_4") (pintype "passive"))
      (node (ref "P7") (pin "A1") (pinfunction "GND_A1") (pintype "bidirectional"))
      (node (ref "P7") (pin "B1") (pinfunction "GND_B1") (pintype "bidirectional"))
      (node (ref "P9") (pin "A1") (pinfunction "GND_A1") (pintype "bidirectional"))
      (node (ref "P9") (pin "B1") (pinfunction "GND_B1") (pintype "bidirectional"))
      (node (ref "PWR") (pin "2") (pinfunction "K_2") (pintype "passive"))
      (node (ref "R10") (pin "2") (pinfunction "2_2") (pintype "passive"))
      (node (ref "R11") (pin "2") (pinfunction "2_2") (pintype "passive"))
      (node (ref "R18") (pin "1") (pinfunction "1_1") (pintype "passive"))
      (node (ref "R21") (pin "1") (pinfunction "1_1") (pintype "passive"))
      (node (ref "R8") (pin "1") (pinfunction "1_1") (pintype "passive"))
      (node (ref "R9") (pin "1") (pinfunction "1_1") (pintype "passive"))
      (node (ref "S1") (pin "3") (pinfunction "B1_3") (pintype "passive"))
      (node (ref "S2") (pin "3") (pinfunction "B1_3") (pintype "passive"))
      (node (ref "S5") (pin "2") (pinfunction "2_2") (pintype "passive"))
      (node (ref "U1") (pin "1") (pinfunction "GND_1") (pintype "passive"))
      (node (ref "U2") (pin "10") (pinfunction "VSS_5_10") (pintype "power_in"))
      (node (ref "U2") (pin "19") (pinfunction "VSSA_19") (pintype "power_in"))
      (node (ref "U2") (pin "27") (pinfunction "VSS_4_27") (pintype "power_in"))
      (node (ref "U2") (pin "49") (pinfunction "VSS_1_49") (pintype "power_in"))
      (node (ref "U2") (pin "74") (pinfunction "VSS_2_74") (pintype "power_in"))
      (node (ref "U2") (pin "99") (pinfunction "VSS_3_99") (pintype "power_in"))
      (node (ref "U3") (pin "18") (pinfunction "VSS/GND_18") (pintype "power_in"))
    )
    (net (code "119") (name "Net-(D2-K)") (class "Default")
      (node (ref "D2") (pin "2") (pinfunction "K_2") (pintype "passive"))
      (node (ref "R13") (pin "2") (pinfunction "2_2") (pintype "passive"))
    )
    (net (code "120") (name "Net-(D3-K)") (class "Default")
      (node (ref "D3") (pin "2") (pinfunction "K_2") (pintype "passive"))
      (node (ref "R21") (pin "2") (pinfunction "2_2") (pintype "passive"))
    )
    (net (code "121") (name "Net-(J3-Pad6)") (class "Default")
      (node (ref "J3") (pin "6") (pinfunction "6_6") (pintype "passive"))
      (node (ref "R5") (pin "1") (pinfunction "1_1") (pintype "passive"))
    )
    (net (code "122") (name "Net-(J3-Pad10)") (class "Default")
      (node (ref "J3") (pin "10") (pinfunction "10_10") (pintype "passive"))
      (node (ref "J5") (pin "1") (pinfunction "1_1") (pintype "passive"))
    )
    (net (code "123") (name "Net-(LED1-A)") (class "Default")
      (node (ref "LED1") (pin "1") (pinfunction "A_1") (pintype "passive"))
      (node (ref "R2") (pin "2") (pinfunction "2_2") (pintype "passive"))
    )
    (net (code "124") (name "Net-(LED2-A)") (class "Default")
      (node (ref "LED2") (pin "1") (pinfunction "A_1") (pintype "passive"))
      (node (ref "R3") (pin "2") (pinfunction "2_2") (pintype "passive"))
    )
    (net (code "125") (name "Net-(P7-CC-PadA5)") (class "Default")
      (node (ref "P7") (pin "A5") (pinfunction "CC_A5") (pintype "bidirectional"))
      (node (ref "R8") (pin "2") (pinfunction "2_2") (pintype "passive"))
    )
    (net (code "126") (name "Net-(P7-CC-PadB5)") (class "Default")
      (node (ref "P7") (pin "B5") (pinfunction "CC_B5") (pintype "bidirectional"))
      (node (ref "R9") (pin "2") (pinfunction "2_2") (pintype "passive"))
    )
    (net (code "127") (name "Net-(P9-CC-PadA5)") (class "Default")
      (node (ref "P9") (pin "A5") (pinfunction "CC_A5") (pintype "bidirectional"))
      (node (ref "R10") (pin "1") (pinfunction "1_1") (pintype "passive"))
    )
    (net (code "128") (name "Net-(P9-CC-PadB5)") (class "Default")
      (node (ref "P9") (pin "B5") (pinfunction "CC_B5") (pintype "bidirectional"))
      (node (ref "R11") (pin "1") (pinfunction "1_1") (pintype "passive"))
    )
    (net (code "129") (name "Net-(PWR-A)") (class "Default")
      (node (ref "PWR") (pin "1") (pinfunction "A_1") (pintype "passive"))
      (node (ref "R1") (pin "1") (pinfunction "1_1") (pintype "passive"))
    )
    (net (code "130") (name "Net-(U1-VOUT)") (class "Default")
      (node (ref "C13") (pin "1") (pinfunction "1_1") (pintype "passive"))
      (node (ref "S3") (pin "1") (pinfunction "1_1") (pintype "passive"))
      (node (ref "U1") (pin "2") (pinfunction "VOUT_2") (pintype "passive"))
    )
    (net (code "131") (name "unconnected-(P7-RFU1-PadA8)") (class "Default")
      (node (ref "P7") (pin "A8") (pinfunction "RFU1_A8") (pintype "bidirectional+no_connect"))
    )
    (net (code "132") (name "unconnected-(P7-RFU1-PadB8)") (class "Default")
      (node (ref "P7") (pin "B8") (pinfunction "RFU1_B8") (pintype "bidirectional+no_connect"))
    )
    (net (code "133") (name "unconnected-(P9-RFU1-PadA8)") (class "Default")
      (node (ref "P9") (pin "A8") (pinfunction "RFU1_A8") (pintype "bidirectional+no_connect"))
    )
    (net (code "134") (name "unconnected-(P9-RFU1-PadB8)") (class "Default")
      (node (ref "P9") (pin "B8") (pinfunction "RFU1_B8") (pintype "bidirectional+no_connect"))
    )
    (net (code "135") (name "unconnected-(S1-A1-Pad4)") (class "Default")
      (node (ref "S1") (pin "4") (pinfunction "A1_4") (pintype "passive"))
    )
    (net (code "136") (name "unconnected-(S1-B0-Pad2)") (class "Default")
      (node (ref "S1") (pin "2") (pinfunction "B0_2") (pintype "passive"))
    )
    (net (code "137") (name "unconnected-(S2-A1-Pad4)") (class "Default")
      (node (ref "S2") (pin "4") (pinfunction "A1_4") (pintype "passive"))
    )
    (net (code "138") (name "unconnected-(S2-B0-Pad2)") (class "Default")
      (node (ref "S2") (pin "2") (pinfunction "B0_2") (pintype "passive"))
    )
    (net (code "139") (name "unconnected-(S3-Pad2)") (class "Default")
      (node (ref "S3") (pin "2") (pinfunction "2_2") (pintype "passive"))
    )
    (net (code "140") (name "unconnected-(U3-PA5{slash}UART1_CTS{slash}PA1_(no5V)-Pad2)") (class "Default")
      (node (ref "U3") (pin "2") (pinfunction "PA5/UART1_CTS/PA1_(no5V)_2") (pintype "bidirectional+no_connect"))
    )
    (net (code "141") (name "unconnected-(U3-PB12{slash}SPI2_NSS{slash}CAN2_RX-Pad5)") (class "Default")
      (node (ref "U3") (pin "5") (pinfunction "PB12/SPI2_NSS/CAN2_RX_5") (pintype "bidirectional+no_connect"))
    )
    (net (code "142") (name "unconnected-(U3-PB14{slash}SPI2_MISO{slash}UART3_RTS-Pad7)") (class "Default")
      (node (ref "U3") (pin "7") (pinfunction "PB14/SPI2_MISO/UART3_RTS_7") (pintype "bidirectional+no_connect"))
    )
    (net (code "143") (name "unconnected-(U3-PB15{slash}SPI2_MOSI{slash}UART1_TX-Pad8)") (class "Default")
      (node (ref "U3") (pin "8") (pinfunction "PB15/SPI2_MOSI/UART1_TX_8") (pintype "bidirectional+no_connect"))
    )
  )
)
